# lm75_breakout_soic8_sot23.net
KiCad netlist of a schematic drawn in EAGLE
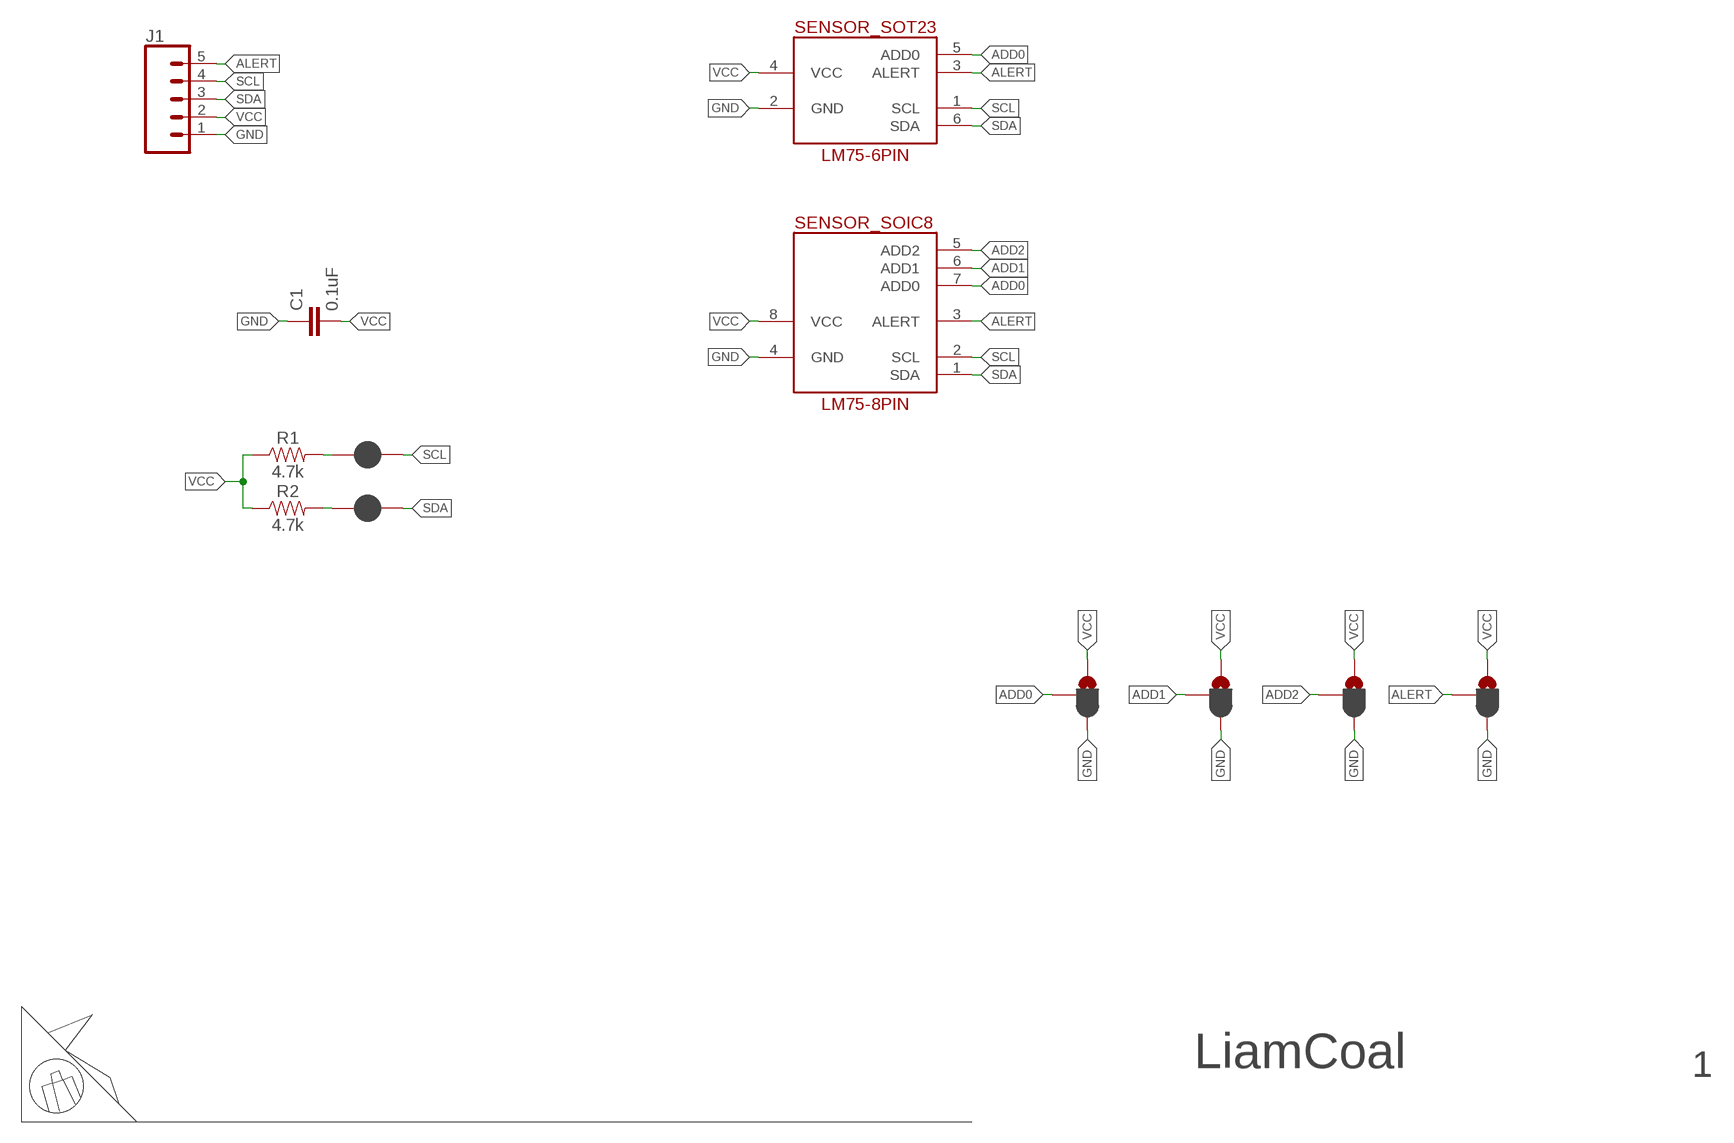
[diagram p0: schematic, sheet 1]

(export (version "E")
  (design (tool "Eeschema 10.0.6"))
  (components
    (comp (ref "C1")
      (value "0.1uF")
      (footprint "eagle-import:0603")
      (libsource (lib "eagle-import") (part "0.1UF-0603-100V-10%"))
    )
    (comp (ref "J1")
      (value "CONN_05NO_SILK")
      (footprint "eagle-import:1X05_NO_SILK")
      (libsource (lib "eagle-import") (part "CONN_05NO_SILK"))
    )
    (comp (ref "JP1")
      (value "JUMPER-SMT_3_1-NC_PASTE_SILK")
      (footprint "eagle-import:SMT-JUMPER_3_1-NC_PASTE_SILK")
      (libsource (lib "eagle-import") (part "JUMPER-SMT_3_1-NC_PASTE_SILK"))
    )
    (comp (ref "JP2")
      (value "JUMPER-SMT_3_1-NC_PASTE_SILK")
      (footprint "eagle-import:SMT-JUMPER_3_1-NC_PASTE_SILK")
      (libsource (lib "eagle-import") (part "JUMPER-SMT_3_1-NC_PASTE_SILK"))
    )
    (comp (ref "JP3")
      (value "JUMPER-SMT_3_1-NC_PASTE_SILK")
      (footprint "eagle-import:SMT-JUMPER_3_1-NC_PASTE_SILK")
      (libsource (lib "eagle-import") (part "JUMPER-SMT_3_1-NC_PASTE_SILK"))
    )
    (comp (ref "JP4")
      (value "JUMPER-SMT_2_NC_PASTE_SILK")
      (footprint "eagle-import:SMT-JUMPER_2_NC_PASTE_SILK")
      (libsource (lib "eagle-import") (part "JUMPER-SMT_2_NC_PASTE_SILK"))
    )
    (comp (ref "JP5")
      (value "JUMPER-SMT_2_NC_PASTE_SILK")
      (footprint "eagle-import:SMT-JUMPER_2_NC_PASTE_SILK")
      (libsource (lib "eagle-import") (part "JUMPER-SMT_2_NC_PASTE_SILK"))
    )
    (comp (ref "JP6")
      (value "JUMPER-SMT_3_1-NC_PASTE_SILK")
      (footprint "eagle-import:SMT-JUMPER_3_1-NC_PASTE_SILK")
      (libsource (lib "eagle-import") (part "JUMPER-SMT_3_1-NC_PASTE_SILK"))
    )
    (comp (ref "R1")
      (value "4.7k")
      (footprint "eagle-import:0603")
      (libsource (lib "eagle-import") (part "4.7KOHM-0603-1/10W-1%"))
    )
    (comp (ref "R2")
      (value "4.7k")
      (footprint "eagle-import:0603")
      (libsource (lib "eagle-import") (part "4.7KOHM-0603-1/10W-1%"))
    )
    (comp (ref "SENSOR_SOIC8")
      (value "LM75-8PIN")
      (footprint "eagle-import:SOIC8")
      (libsource (lib "eagle-import") (part "LM75-8PIN"))
    )
    (comp (ref "SENSOR_SOT23")
      (value "LM75-6PIN")
      (footprint "eagle-import:SOT23-6")
      (libsource (lib "eagle-import") (part "LM75-6PIN"))
    )
  )
  (nets
    (net (code "1") (name "ADD0") (class "Default")
      (node (ref "JP1") (pin "2") (pinfunction "2_2") (pintype "passive"))
      (node (ref "SENSOR_SOIC8") (pin "7") (pinfunction "ADD0_7") (pintype "bidirectional"))
      (node (ref "SENSOR_SOT23") (pin "5") (pinfunction "ADD0_5") (pintype "bidirectional"))
    )
    (net (code "2") (name "ADD1") (class "Default")
      (node (ref "JP2") (pin "2") (pinfunction "2_2") (pintype "passive"))
      (node (ref "SENSOR_SOIC8") (pin "6") (pinfunction "ADD1_6") (pintype "bidirectional"))
    )
    (net (code "3") (name "ADD2") (class "Default")
      (node (ref "JP3") (pin "2") (pinfunction "2_2") (pintype "passive"))
      (node (ref "SENSOR_SOIC8") (pin "5") (pinfunction "ADD2_5") (pintype "bidirectional"))
    )
    (net (code "4") (name "ALERT") (class "Default")
      (node (ref "J1") (pin "5") (pinfunction "5_5") (pintype "passive"))
      (node (ref "JP6") (pin "2") (pinfunction "2_2") (pintype "passive"))
      (node (ref "SENSOR_SOIC8") (pin "3") (pinfunction "ALERT_3") (pintype "bidirectional"))
      (node (ref "SENSOR_SOT23") (pin "3") (pinfunction "ALERT_3") (pintype "bidirectional"))
    )
    (net (code "5") (name "GND") (class "Default")
      (node (ref "C1") (pin "1") (pinfunction "1_1") (pintype "passive"))
      (node (ref "J1") (pin "1") (pinfunction "1_1") (pintype "passive"))
      (node (ref "JP1") (pin "3") (pinfunction "3_3") (pintype "passive"))
      (node (ref "JP2") (pin "3") (pinfunction "3_3") (pintype "passive"))
      (node (ref "JP3") (pin "3") (pinfunction "3_3") (pintype "passive"))
      (node (ref "JP6") (pin "3") (pinfunction "3_3") (pintype "passive"))
      (node (ref "SENSOR_SOIC8") (pin "4") (pinfunction "GND_4") (pintype "bidirectional"))
      (node (ref "SENSOR_SOT23") (pin "2") (pinfunction "GND_2") (pintype "bidirectional"))
    )
    (net (code "6") (name "Net-(JP4-Pad1)") (class "Default")
      (node (ref "JP4") (pin "1") (pinfunction "1_1") (pintype "passive"))
      (node (ref "R1") (pin "2") (pinfunction "2_2") (pintype "passive"))
    )
    (net (code "7") (name "Net-(JP5-Pad1)") (class "Default")
      (node (ref "JP5") (pin "1") (pinfunction "1_1") (pintype "passive"))
      (node (ref "R2") (pin "2") (pinfunction "2_2") (pintype "passive"))
    )
    (net (code "8") (name "SCL") (class "Default")
      (node (ref "J1") (pin "4") (pinfunction "4_4") (pintype "passive"))
      (node (ref "JP4") (pin "2") (pinfunction "2_2") (pintype "passive"))
      (node (ref "SENSOR_SOIC8") (pin "2") (pinfunction "SCL_2") (pintype "bidirectional"))
      (node (ref "SENSOR_SOT23") (pin "1") (pinfunction "SCL_1") (pintype "bidirectional"))
    )
    (net (code "9") (name "SDA") (class "Default")
      (node (ref "J1") (pin "3") (pinfunction "3_3") (pintype "passive"))
      (node (ref "JP5") (pin "2") (pinfunction "2_2") (pintype "passive"))
      (node (ref "SENSOR_SOIC8") (pin "1") (pinfunction "SDA_1") (pintype "bidirectional"))
      (node (ref "SENSOR_SOT23") (pin "6") (pinfunction "SDA_6") (pintype "bidirectional"))
    )
    (net (code "10") (name "VCC") (class "Default")
      (node (ref "C1") (pin "2") (pinfunction "2_2") (pintype "passive"))
      (node (ref "J1") (pin "2") (pinfunction "2_2") (pintype "passive"))
      (node (ref "JP1") (pin "1") (pinfunction "1_1") (pintype "passive"))
      (node (ref "JP2") (pin "1") (pinfunction "1_1") (pintype "passive"))
      (node (ref "JP3") (pin "1") (pinfunction "1_1") (pintype "passive"))
      (node (ref "JP6") (pin "1") (pinfunction "1_1") (pintype "passive"))
      (node (ref "R1") (pin "1") (pinfunction "1_1") (pintype "passive"))
      (node (ref "R2") (pin "1") (pinfunction "1_1") (pintype "passive"))
      (node (ref "SENSOR_SOIC8") (pin "8") (pinfunction "VCC_8") (pintype "bidirectional"))
      (node (ref "SENSOR_SOT23") (pin "4") (pinfunction "VCC_4") (pintype "bidirectional"))
    )
  )
)
